# SwimWatch2_1.net
KiCad netlist of a schematic drawn in EAGLE
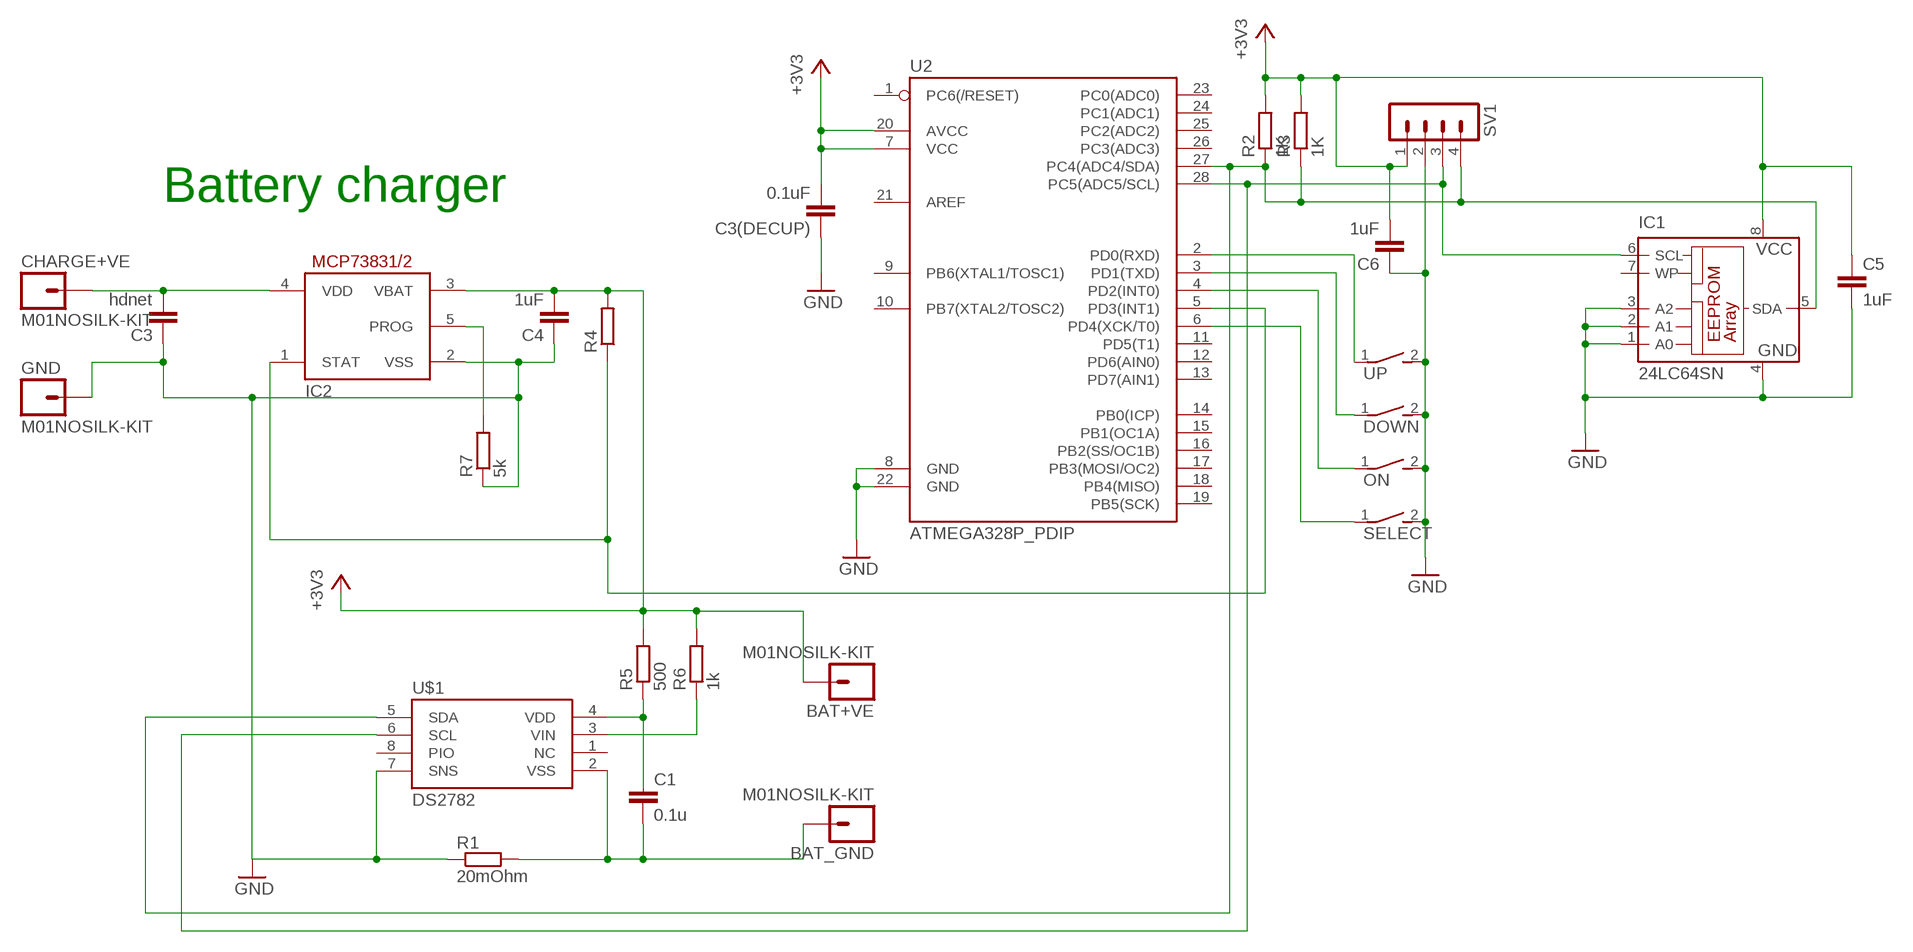
[diagram p0: schematic, sheet 1]

(export (version "E")
  (design (tool "Eeschema 10.0.6"))
  (components
    (comp (ref "BAT+VE")
      (value "M01NOSILK-KIT")
      (footprint "eagle-import:1X01NS-KIT")
      (libsource (lib "eagle-import") (part "M01NOSILK-KIT"))
    )
    (comp (ref "BAT_GND")
      (value "M01NOSILK-KIT")
      (footprint "eagle-import:1X01NS-KIT")
      (libsource (lib "eagle-import") (part "M01NOSILK-KIT"))
    )
    (comp (ref "C1")
      (value "0.1u")
      (footprint "eagle-import:C025-030X050")
      (libsource (lib "eagle-import") (part "C-EU025-030X050"))
    )
    (comp (ref "C3")
      (value "hdnet")
      (footprint "eagle-import:C0805")
      (libsource (lib "eagle-import") (part "C-EUC0805"))
    )
    (comp (ref "C3(DECUP)")
      (value "0.1uF")
      (footprint "eagle-import:C0805")
      (libsource (lib "eagle-import") (part "C-EUC0805"))
    )
    (comp (ref "C4")
      (value "1uF")
      (footprint "eagle-import:C0805")
      (libsource (lib "eagle-import") (part "C-EUC0805"))
    )
    (comp (ref "C5")
      (value "1uF")
      (footprint "eagle-import:C0805")
      (libsource (lib "eagle-import") (part "C-EUC0805"))
    )
    (comp (ref "C6")
      (value "1uF")
      (footprint "eagle-import:C0805")
      (libsource (lib "eagle-import") (part "C-EUC0805"))
    )
    (comp (ref "CHARGE+VE")
      (value "M01NOSILK-KIT")
      (footprint "eagle-import:1X01NS-KIT")
      (libsource (lib "eagle-import") (part "M01NOSILK-KIT"))
    )
    (comp (ref "DOWN")
      (value "DS01E")
      (footprint "eagle-import:DS-01")
      (libsource (lib "eagle-import") (part "DS01E"))
    )
    (comp (ref "GND")
      (value "M01NOSILK-KIT")
      (footprint "eagle-import:1X01NS-KIT")
      (libsource (lib "eagle-import") (part "M01NOSILK-KIT"))
    )
    (comp (ref "IC1")
      (value "24LC64SN")
      (footprint "eagle-import:SO-08")
      (fields (field (name "MF") "MICROCHIP") (field (name "MPN") "24LC64-I/SN"))
      (libsource (lib "eagle-import") (part "24SNLC64"))
    )
    (comp (ref "IC2")
      (value "MCP73831/OT")
      (footprint "eagle-import:SOT23-5L")
      (libsource (lib "eagle-import") (part "MCP73831/OT"))
    )
    (comp (ref "ON")
      (value "DS01E")
      (footprint "eagle-import:DS-01")
      (libsource (lib "eagle-import") (part "DS01E"))
    )
    (comp (ref "R1")
      (value "20mOhm")
      (footprint "eagle-import:0204_5")
      (libsource (lib "eagle-import") (part "R-EU_0204/5"))
    )
    (comp (ref "R2")
      (value "1K")
      (footprint "eagle-import:M0805")
      (libsource (lib "eagle-import") (part "R-EU_M0805"))
    )
    (comp (ref "R3")
      (value "1K")
      (footprint "eagle-import:M0805")
      (libsource (lib "eagle-import") (part "R-EU_M0805"))
    )
    (comp (ref "R4")
      (value "R-EU_0204/5")
      (footprint "eagle-import:0204_5")
      (libsource (lib "eagle-import") (part "R-EU_0204/5"))
    )
    (comp (ref "R5")
      (value "500")
      (footprint "eagle-import:0204_5")
      (libsource (lib "eagle-import") (part "R-EU_0204/5"))
    )
    (comp (ref "R6")
      (value "1k")
      (footprint "eagle-import:0204_5")
      (libsource (lib "eagle-import") (part "R-EU_0204/5"))
    )
    (comp (ref "R7")
      (value "5k")
      (footprint "eagle-import:0204_5")
      (libsource (lib "eagle-import") (part "R-EU_0204/5"))
    )
    (comp (ref "SELECT")
      (value "DS01E")
      (footprint "eagle-import:DS-01")
      (libsource (lib "eagle-import") (part "DS01E"))
    )
    (comp (ref "SV1")
      (value "MA04-1")
      (footprint "eagle-import:MA04-1")
      (libsource (lib "eagle-import") (part "MA04-1"))
    )
    (comp (ref "U$1")
      (value "DS2782")
      (footprint "eagle-import:DS2782")
      (libsource (lib "eagle-import") (part "DS2782"))
    )
    (comp (ref "U2")
      (value "ATMEGA328P_PDIP")
      (footprint "eagle-import:DIL28-3")
      (libsource (lib "eagle-import") (part "ATMEGA328P_PDIP"))
    )
    (comp (ref "UP")
      (value "DS01E")
      (footprint "eagle-import:DS-01")
      (libsource (lib "eagle-import") (part "DS01E"))
    )
  )
  (nets
    (net (code "1") (name "+3V3") (class "Default")
      (node (ref "BAT+VE") (pin "1") (pinfunction "1_1") (pintype "passive"))
      (node (ref "C3(DECUP)") (pin "2") (pinfunction "2_2") (pintype "passive"))
      (node (ref "C4") (pin "2") (pinfunction "2_2") (pintype "passive"))
      (node (ref "C5") (pin "1") (pinfunction "1_1") (pintype "passive"))
      (node (ref "C6") (pin "2") (pinfunction "2_2") (pintype "passive"))
      (node (ref "IC1") (pin "8") (pinfunction "VCC_8") (pintype "power_in"))
      (node (ref "IC2") (pin "3") (pinfunction "VBAT_3") (pintype "bidirectional"))
      (node (ref "R2") (pin "2") (pinfunction "2_2") (pintype "passive"))
      (node (ref "R3") (pin "2") (pinfunction "2_2") (pintype "passive"))
      (node (ref "R4") (pin "2") (pinfunction "2_2") (pintype "passive"))
      (node (ref "R5") (pin "2") (pinfunction "2_2") (pintype "passive"))
      (node (ref "R6") (pin "2") (pinfunction "2_2") (pintype "passive"))
      (node (ref "SV1") (pin "1") (pinfunction "1_1") (pintype "passive"))
      (node (ref "U2") (pin "20") (pinfunction "AVCC_20") (pintype "bidirectional"))
      (node (ref "U2") (pin "7") (pinfunction "VCC_7") (pintype "bidirectional"))
    )
    (net (code "2") (name "GND") (class "Default")
      (node (ref "C3") (pin "1") (pinfunction "1_1") (pintype "passive"))
      (node (ref "C3(DECUP)") (pin "1") (pinfunction "1_1") (pintype "passive"))
      (node (ref "C4") (pin "1") (pinfunction "1_1") (pintype "passive"))
      (node (ref "C5") (pin "2") (pinfunction "2_2") (pintype "passive"))
      (node (ref "C6") (pin "1") (pinfunction "1_1") (pintype "passive"))
      (node (ref "DOWN") (pin "2") (pinfunction "2_2") (pintype "passive"))
      (node (ref "GND") (pin "1") (pinfunction "1_1") (pintype "passive"))
      (node (ref "IC1") (pin "1") (pinfunction "A0_1") (pintype "input"))
      (node (ref "IC1") (pin "2") (pinfunction "A1_2") (pintype "input"))
      (node (ref "IC1") (pin "3") (pinfunction "A2_3") (pintype "input"))
      (node (ref "IC1") (pin "4") (pinfunction "GND_4") (pintype "power_in"))
      (node (ref "IC2") (pin "2") (pinfunction "VSS_2") (pintype "power_in"))
      (node (ref "ON") (pin "2") (pinfunction "2_2") (pintype "passive"))
      (node (ref "R1") (pin "1") (pinfunction "1_1") (pintype "passive"))
      (node (ref "R7") (pin "1") (pinfunction "1_1") (pintype "passive"))
      (node (ref "SELECT") (pin "2") (pinfunction "2_2") (pintype "passive"))
      (node (ref "SV1") (pin "2") (pinfunction "2_2") (pintype "passive"))
      (node (ref "U$1") (pin "7") (pinfunction "SNS_7") (pintype "bidirectional"))
      (node (ref "U2") (pin "22") (pinfunction "GND_22") (pintype "bidirectional"))
      (node (ref "U2") (pin "8") (pinfunction "GND_8") (pintype "bidirectional"))
      (node (ref "UP") (pin "2") (pinfunction "2_2") (pintype "passive"))
    )
    (net (code "3") (name "Net-(IC1-SCL)") (class "Default")
      (node (ref "IC1") (pin "6") (pinfunction "SCL_6") (pintype "input"))
      (node (ref "SV1") (pin "3") (pinfunction "3_3") (pintype "passive"))
      (node (ref "U$1") (pin "6") (pinfunction "SCL_6") (pintype "bidirectional"))
      (node (ref "U2") (pin "28") (pinfunction "PC5(ADC5/SCL)_28") (pintype "bidirectional"))
    )
    (net (code "4") (name "Net-(IC1-SDA)") (class "Default")
      (node (ref "IC1") (pin "5") (pinfunction "SDA_5") (pintype "bidirectional"))
      (node (ref "R2") (pin "1") (pinfunction "1_1") (pintype "passive"))
      (node (ref "R3") (pin "1") (pinfunction "1_1") (pintype "passive"))
      (node (ref "SV1") (pin "4") (pinfunction "4_4") (pintype "passive"))
      (node (ref "U$1") (pin "5") (pinfunction "SDA_5") (pintype "bidirectional"))
      (node (ref "U2") (pin "27") (pinfunction "PC4(ADC4/SDA)_27") (pintype "bidirectional"))
    )
    (net (code "5") (name "Net-(IC2-PROG)") (class "Default")
      (node (ref "IC2") (pin "5") (pinfunction "PROG_5") (pintype "input"))
      (node (ref "R7") (pin "2") (pinfunction "2_2") (pintype "passive"))
    )
    (net (code "6") (name "Net-(IC2-STAT)") (class "Default")
      (node (ref "IC2") (pin "1") (pinfunction "STAT_1") (pintype "output"))
      (node (ref "R4") (pin "1") (pinfunction "1_1") (pintype "passive"))
      (node (ref "U2") (pin "5") (pinfunction "PD3(INT1)_5") (pintype "bidirectional"))
    )
    (net (code "7") (name "Net-(IC2-VDD)") (class "Default")
      (node (ref "C3") (pin "2") (pinfunction "2_2") (pintype "passive"))
      (node (ref "CHARGE+VE") (pin "1") (pinfunction "1_1") (pintype "passive"))
      (node (ref "IC2") (pin "4") (pinfunction "VDD_4") (pintype "power_in"))
    )
    (net (code "8") (name "Net-(U$1-VDD)") (class "Default")
      (node (ref "R5") (pin "1") (pinfunction "1_1") (pintype "passive"))
      (node (ref "U$1") (pin "4") (pinfunction "VDD_4") (pintype "bidirectional"))
    )
    (net (code "9") (name "Net-(U$1-VIN)") (class "Default")
      (node (ref "R6") (pin "1") (pinfunction "1_1") (pintype "passive"))
      (node (ref "U$1") (pin "3") (pinfunction "VIN_3") (pintype "bidirectional"))
    )
    (net (code "10") (name "Net-(U$1-VSS)") (class "Default")
      (node (ref "BAT_GND") (pin "1") (pinfunction "1_1") (pintype "passive"))
      (node (ref "C1") (pin "2") (pinfunction "2_2") (pintype "passive"))
      (node (ref "R1") (pin "2") (pinfunction "2_2") (pintype "passive"))
      (node (ref "U$1") (pin "2") (pinfunction "VSS_2") (pintype "bidirectional"))
    )
    (net (code "11") (name "Net-(U2-PD0(RXD))") (class "Default")
      (node (ref "U2") (pin "2") (pinfunction "PD0(RXD)_2") (pintype "bidirectional"))
      (node (ref "UP") (pin "1") (pinfunction "1_1") (pintype "passive"))
    )
    (net (code "12") (name "Net-(U2-PD1(TXD))") (class "Default")
      (node (ref "DOWN") (pin "1") (pinfunction "1_1") (pintype "passive"))
      (node (ref "U2") (pin "3") (pinfunction "PD1(TXD)_3") (pintype "bidirectional"))
    )
    (net (code "13") (name "Net-(U2-PD2(INT0))") (class "Default")
      (node (ref "ON") (pin "1") (pinfunction "1_1") (pintype "passive"))
      (node (ref "U2") (pin "4") (pinfunction "PD2(INT0)_4") (pintype "bidirectional"))
    )
    (net (code "14") (name "Net-(U2-PD4(XCK{slash}T0))") (class "Default")
      (node (ref "SELECT") (pin "1") (pinfunction "1_1") (pintype "passive"))
      (node (ref "U2") (pin "6") (pinfunction "PD4(XCK/T0)_6") (pintype "bidirectional"))
    )
    (net (code "15") (name "unconnected-(C1-Pad1)") (class "Default")
      (node (ref "C1") (pin "1") (pinfunction "1_1") (pintype "passive"))
    )
    (net (code "16") (name "unconnected-(IC1-WP-Pad7)") (class "Default")
      (node (ref "IC1") (pin "7") (pinfunction "WP_7") (pintype "input"))
    )
    (net (code "17") (name "unconnected-(U$1-NC-Pad1)") (class "Default")
      (node (ref "U$1") (pin "1") (pinfunction "NC_1") (pintype "bidirectional"))
    )
    (net (code "18") (name "unconnected-(U$1-PIO-Pad8)") (class "Default")
      (node (ref "U$1") (pin "8") (pinfunction "PIO_8") (pintype "bidirectional"))
    )
    (net (code "19") (name "unconnected-(U2-AREF-Pad21)") (class "Default")
      (node (ref "U2") (pin "21") (pinfunction "AREF_21") (pintype "bidirectional"))
    )
    (net (code "20") (name "unconnected-(U2-PB0(ICP)-Pad14)") (class "Default")
      (node (ref "U2") (pin "14") (pinfunction "PB0(ICP)_14") (pintype "bidirectional"))
    )
    (net (code "21") (name "unconnected-(U2-PB1(OC1A)-Pad15)") (class "Default")
      (node (ref "U2") (pin "15") (pinfunction "PB1(OC1A)_15") (pintype "bidirectional"))
    )
    (net (code "22") (name "unconnected-(U2-PB2(SS{slash}OC1B)-Pad16)") (class "Default")
      (node (ref "U2") (pin "16") (pinfunction "PB2(SS/OC1B)_16") (pintype "bidirectional"))
    )
    (net (code "23") (name "unconnected-(U2-PB3(MOSI{slash}OC2)-Pad17)") (class "Default")
      (node (ref "U2") (pin "17") (pinfunction "PB3(MOSI/OC2)_17") (pintype "bidirectional"))
    )
    (net (code "24") (name "unconnected-(U2-PB4(MISO)-Pad18)") (class "Default")
      (node (ref "U2") (pin "18") (pinfunction "PB4(MISO)_18") (pintype "bidirectional"))
    )
    (net (code "25") (name "unconnected-(U2-PB5(SCK)-Pad19)") (class "Default")
      (node (ref "U2") (pin "19") (pinfunction "PB5(SCK)_19") (pintype "bidirectional"))
    )
    (net (code "26") (name "unconnected-(U2-PB6(XTAL1{slash}TOSC1)-Pad9)") (class "Default")
      (node (ref "U2") (pin "9") (pinfunction "PB6(XTAL1/TOSC1)_9") (pintype "bidirectional"))
    )
    (net (code "27") (name "unconnected-(U2-PB7(XTAL2{slash}TOSC2)-Pad10)") (class "Default")
      (node (ref "U2") (pin "10") (pinfunction "PB7(XTAL2/TOSC2)_10") (pintype "bidirectional"))
    )
    (net (code "28") (name "unconnected-(U2-PC0(ADC0)-Pad23)") (class "Default")
      (node (ref "U2") (pin "23") (pinfunction "PC0(ADC0)_23") (pintype "bidirectional"))
    )
    (net (code "29") (name "unconnected-(U2-PC1(ADC1)-Pad24)") (class "Default")
      (node (ref "U2") (pin "24") (pinfunction "PC1(ADC1)_24") (pintype "bidirectional"))
    )
    (net (code "30") (name "unconnected-(U2-PC2(ADC2)-Pad25)") (class "Default")
      (node (ref "U2") (pin "25") (pinfunction "PC2(ADC2)_25") (pintype "bidirectional"))
    )
    (net (code "31") (name "unconnected-(U2-PC3(ADC3)-Pad26)") (class "Default")
      (node (ref "U2") (pin "26") (pinfunction "PC3(ADC3)_26") (pintype "bidirectional"))
    )
    (net (code "32") (name "unconnected-(U2-PC6({slash}RESET)-Pad1)") (class "Default")
      (node (ref "U2") (pin "1") (pinfunction "PC6(/RESET)_1") (pintype "bidirectional"))
    )
    (net (code "33") (name "unconnected-(U2-PD5(T1)-Pad11)") (class "Default")
      (node (ref "U2") (pin "11") (pinfunction "PD5(T1)_11") (pintype "bidirectional"))
    )
    (net (code "34") (name "unconnected-(U2-PD6(AIN0)-Pad12)") (class "Default")
      (node (ref "U2") (pin "12") (pinfunction "PD6(AIN0)_12") (pintype "bidirectional"))
    )
    (net (code "35") (name "unconnected-(U2-PD7(AIN1)-Pad13)") (class "Default")
      (node (ref "U2") (pin "13") (pinfunction "PD7(AIN1)_13") (pintype "bidirectional"))
    )
  )
)
